# HighwaySchematic.net
KiCad netlist of a schematic drawn in EasyEDA Pro
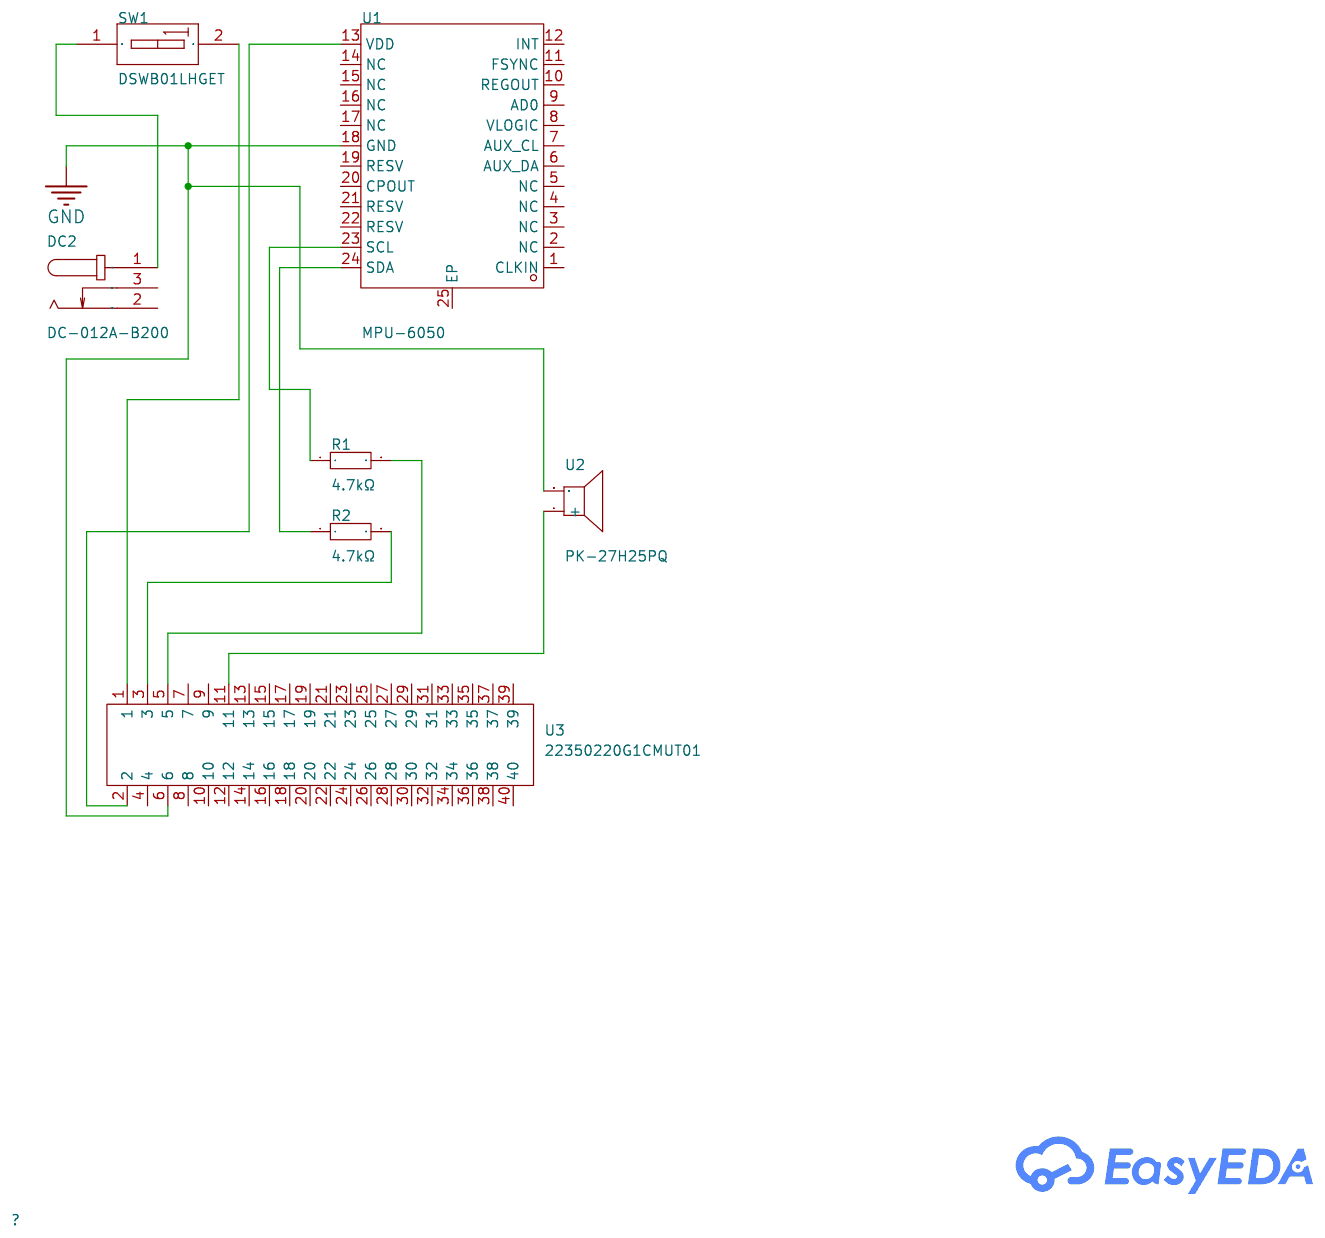
[diagram p0: schematic sheet]

(export (version "E")
  (design (tool "Eeschema 10.0.6"))
  (components
    (comp (ref "DC2")
      (value "DC-012A-B200")
      (footprint "easyedapro:DC-IN-TH_DC-012A-B200")
      (fields (field (name "Manufacturer") "XUNPU(讯普)"))
      (libsource (lib "easyedapro") (part "DC-012A-B200"))
    )
    (comp (ref "R1")
      (value "4.7kΩ")
      (footprint "easyedapro:R0603")
      (fields (field (name "Manufacturer Part") "RC0603FR-074K7L") (field (name "Manufacturer") "YAGEO(国巨)"))
      (libsource (lib "easyedapro") (part "RC0603FR-074K7L"))
    )
    (comp (ref "R2")
      (value "4.7kΩ")
      (footprint "easyedapro:R0603")
      (fields (field (name "Manufacturer Part") "RC0603FR-074K7L") (field (name "Manufacturer") "YAGEO(国巨)"))
      (libsource (lib "easyedapro") (part "RC0603FR-074K7L"))
    )
    (comp (ref "SW1")
      (value "DSWB01LHGET")
      (footprint "easyedapro:SW-TH_DSWB01LHGET")
      (description "Type:平拨,凸起式 Circuit:SPST Number of Positions:1Bit Lead Pitch:- Operating Life:- Color:Red")
      (fields (field (name "Manufacturer") "YE"))
      (libsource (lib "easyedapro") (part "DSWB01LHGET"))
    )
    (comp (ref "U1")
      (value "MPU-6050")
      (footprint "easyedapro:QFN-24_L4.0-W4.0-P0.50-BL-EP2.7")
      (description "Sensor Type:加速度计陀螺仪 Operating Temperature:-40°C~+85°C Operating Temperature:-40°C~+85°C")
      (fields (field (name "Manufacturer") "TDK InvenSense(应美盛)"))
      (libsource (lib "easyedapro") (part "MPU-6050_C24112"))
    )
    (comp (ref "U2")
      (value "PK-27H25PQ")
      (footprint "easyedapro:BUZ-TH_BD30.0-P15.00-D0.8")
      (fields (field (name "Manufacturer") "Mallory Sonalert Products Inc"))
      (libsource (lib "easyedapro") (part "PK-27H25PQ"))
    )
    (comp (ref "U3")
      (value "22350220G1CMUT01")
      (footprint "easyedapro:HDR-SMD_40P-P2.54-V-F-R2-C20-S6.6-EH")
      (libsource (lib "easyedapro") (part "22350220G1CMUT01"))
    )
  )
  (nets
    (net (code "1") (name "GND") (class "Default")
      (node (ref "U1") (pin "18") (pinfunction "GND_18") (pintype "unspecified"))
      (node (ref "U2") (pin "2") (pinfunction "2_2") (pintype "unspecified"))
      (node (ref "U3") (pin "6") (pinfunction "6_6") (pintype "unspecified"))
    )
    (net (code "2") (name "Net-(R1-Pad2)") (class "Default")
      (node (ref "R1") (pin "2") (pinfunction "2_2") (pintype "input"))
      (node (ref "U3") (pin "5") (pinfunction "5_5") (pintype "unspecified"))
    )
    (net (code "3") (name "Net-(R2-Pad2)") (class "Default")
      (node (ref "R2") (pin "2") (pinfunction "2_2") (pintype "input"))
      (node (ref "U3") (pin "3") (pinfunction "3_3") (pintype "unspecified"))
    )
    (net (code "4") (name "Net-(SW1-A1)") (class "Default")
      (node (ref "DC2") (pin "1") (pinfunction "1_1") (pintype "unspecified"))
      (node (ref "SW1") (pin "1") (pinfunction "A1_1") (pintype "input"))
    )
    (net (code "5") (name "Net-(SW1-Pad2)") (class "Default")
      (node (ref "SW1") (pin "2") (pinfunction "2_2") (pintype "input"))
      (node (ref "U3") (pin "1") (pinfunction "1_1") (pintype "unspecified"))
    )
    (net (code "6") (name "Net-(U1-SCL)") (class "Default")
      (node (ref "R1") (pin "1") (pinfunction "1_1") (pintype "input"))
      (node (ref "U1") (pin "23") (pinfunction "SCL_23") (pintype "unspecified"))
    )
    (net (code "7") (name "Net-(U1-SDA)") (class "Default")
      (node (ref "R2") (pin "1") (pinfunction "1_1") (pintype "input"))
      (node (ref "U1") (pin "24") (pinfunction "SDA_24") (pintype "unspecified"))
    )
    (net (code "8") (name "Net-(U1-VDD)") (class "Default")
      (node (ref "U1") (pin "13") (pinfunction "VDD_13") (pintype "unspecified"))
      (node (ref "U3") (pin "2") (pinfunction "2_2") (pintype "unspecified"))
    )
    (net (code "9") (name "Net-(U2-+)") (class "Default")
      (node (ref "U2") (pin "1") (pinfunction "+_1") (pintype "unspecified"))
      (node (ref "U3") (pin "11") (pinfunction "11_11") (pintype "unspecified"))
    )
    (net (code "10") (name "unconnected-(DC2-Pad2)") (class "Default")
      (node (ref "DC2") (pin "2") (pinfunction "2_2") (pintype "unspecified"))
    )
    (net (code "11") (name "unconnected-(DC2-Pad3)") (class "Default")
      (node (ref "DC2") (pin "3") (pinfunction "3_3") (pintype "unspecified"))
    )
    (net (code "12") (name "unconnected-(U1-AD0-Pad9)") (class "Default")
      (node (ref "U1") (pin "9") (pinfunction "AD0_9") (pintype "unspecified"))
    )
    (net (code "13") (name "unconnected-(U1-AUX_CL-Pad7)") (class "Default")
      (node (ref "U1") (pin "7") (pinfunction "AUX_CL_7") (pintype "unspecified"))
    )
    (net (code "14") (name "unconnected-(U1-AUX_DA-Pad6)") (class "Default")
      (node (ref "U1") (pin "6") (pinfunction "AUX_DA_6") (pintype "unspecified"))
    )
    (net (code "15") (name "unconnected-(U1-CLKIN-Pad1)") (class "Default")
      (node (ref "U1") (pin "1") (pinfunction "CLKIN_1") (pintype "unspecified"))
    )
    (net (code "16") (name "unconnected-(U1-CPOUT-Pad20)") (class "Default")
      (node (ref "U1") (pin "20") (pinfunction "CPOUT_20") (pintype "unspecified"))
    )
    (net (code "17") (name "unconnected-(U1-EP-Pad25)") (class "Default")
      (node (ref "U1") (pin "25") (pinfunction "EP_25") (pintype "unspecified"))
    )
    (net (code "18") (name "unconnected-(U1-FSYNC-Pad11)") (class "Default")
      (node (ref "U1") (pin "11") (pinfunction "FSYNC_11") (pintype "unspecified"))
    )
    (net (code "19") (name "unconnected-(U1-INT-Pad12)") (class "Default")
      (node (ref "U1") (pin "12") (pinfunction "INT_12") (pintype "unspecified"))
    )
    (net (code "20") (name "unconnected-(U1-NC-Pad2)") (class "Default")
      (node (ref "U1") (pin "2") (pinfunction "NC_2") (pintype "unspecified"))
    )
    (net (code "21") (name "unconnected-(U1-NC-Pad3)") (class "Default")
      (node (ref "U1") (pin "3") (pinfunction "NC_3") (pintype "unspecified"))
    )
    (net (code "22") (name "unconnected-(U1-NC-Pad4)") (class "Default")
      (node (ref "U1") (pin "4") (pinfunction "NC_4") (pintype "unspecified"))
    )
    (net (code "23") (name "unconnected-(U1-NC-Pad5)") (class "Default")
      (node (ref "U1") (pin "5") (pinfunction "NC_5") (pintype "unspecified"))
    )
    (net (code "24") (name "unconnected-(U1-NC-Pad14)") (class "Default")
      (node (ref "U1") (pin "14") (pinfunction "NC_14") (pintype "unspecified"))
    )
    (net (code "25") (name "unconnected-(U1-NC-Pad15)") (class "Default")
      (node (ref "U1") (pin "15") (pinfunction "NC_15") (pintype "unspecified"))
    )
    (net (code "26") (name "unconnected-(U1-NC-Pad16)") (class "Default")
      (node (ref "U1") (pin "16") (pinfunction "NC_16") (pintype "unspecified"))
    )
    (net (code "27") (name "unconnected-(U1-NC-Pad17)") (class "Default")
      (node (ref "U1") (pin "17") (pinfunction "NC_17") (pintype "unspecified"))
    )
    (net (code "28") (name "unconnected-(U1-REGOUT-Pad10)") (class "Default")
      (node (ref "U1") (pin "10") (pinfunction "REGOUT_10") (pintype "unspecified"))
    )
    (net (code "29") (name "unconnected-(U1-RESV-Pad19)") (class "Default")
      (node (ref "U1") (pin "19") (pinfunction "RESV_19") (pintype "unspecified"))
    )
    (net (code "30") (name "unconnected-(U1-RESV-Pad21)") (class "Default")
      (node (ref "U1") (pin "21") (pinfunction "RESV_21") (pintype "unspecified"))
    )
    (net (code "31") (name "unconnected-(U1-RESV-Pad22)") (class "Default")
      (node (ref "U1") (pin "22") (pinfunction "RESV_22") (pintype "unspecified"))
    )
    (net (code "32") (name "unconnected-(U1-VLOGIC-Pad8)") (class "Default")
      (node (ref "U1") (pin "8") (pinfunction "VLOGIC_8") (pintype "unspecified"))
    )
    (net (code "33") (name "unconnected-(U3-Pad4)") (class "Default")
      (node (ref "U3") (pin "4") (pinfunction "4_4") (pintype "unspecified"))
    )
    (net (code "34") (name "unconnected-(U3-Pad7)") (class "Default")
      (node (ref "U3") (pin "7") (pinfunction "7_7") (pintype "unspecified"))
    )
    (net (code "35") (name "unconnected-(U3-Pad8)") (class "Default")
      (node (ref "U3") (pin "8") (pinfunction "8_8") (pintype "unspecified"))
    )
    (net (code "36") (name "unconnected-(U3-Pad9)") (class "Default")
      (node (ref "U3") (pin "9") (pinfunction "9_9") (pintype "unspecified"))
    )
    (net (code "37") (name "unconnected-(U3-Pad10)") (class "Default")
      (node (ref "U3") (pin "10") (pinfunction "10_10") (pintype "unspecified"))
    )
    (net (code "38") (name "unconnected-(U3-Pad12)") (class "Default")
      (node (ref "U3") (pin "12") (pinfunction "12_12") (pintype "unspecified"))
    )
    (net (code "39") (name "unconnected-(U3-Pad13)") (class "Default")
      (node (ref "U3") (pin "13") (pinfunction "13_13") (pintype "unspecified"))
    )
    (net (code "40") (name "unconnected-(U3-Pad14)") (class "Default")
      (node (ref "U3") (pin "14") (pinfunction "14_14") (pintype "unspecified"))
    )
    (net (code "41") (name "unconnected-(U3-Pad15)") (class "Default")
      (node (ref "U3") (pin "15") (pinfunction "15_15") (pintype "unspecified"))
    )
    (net (code "42") (name "unconnected-(U3-Pad16)") (class "Default")
      (node (ref "U3") (pin "16") (pinfunction "16_16") (pintype "unspecified"))
    )
    (net (code "43") (name "unconnected-(U3-Pad17)") (class "Default")
      (node (ref "U3") (pin "17") (pinfunction "17_17") (pintype "unspecified"))
    )
    (net (code "44") (name "unconnected-(U3-Pad18)") (class "Default")
      (node (ref "U3") (pin "18") (pinfunction "18_18") (pintype "unspecified"))
    )
    (net (code "45") (name "unconnected-(U3-Pad19)") (class "Default")
      (node (ref "U3") (pin "19") (pinfunction "19_19") (pintype "unspecified"))
    )
    (net (code "46") (name "unconnected-(U3-Pad20)") (class "Default")
      (node (ref "U3") (pin "20") (pinfunction "20_20") (pintype "unspecified"))
    )
    (net (code "47") (name "unconnected-(U3-Pad21)") (class "Default")
      (node (ref "U3") (pin "21") (pinfunction "21_21") (pintype "unspecified"))
    )
    (net (code "48") (name "unconnected-(U3-Pad22)") (class "Default")
      (node (ref "U3") (pin "22") (pinfunction "22_22") (pintype "unspecified"))
    )
    (net (code "49") (name "unconnected-(U3-Pad23)") (class "Default")
      (node (ref "U3") (pin "23") (pinfunction "23_23") (pintype "unspecified"))
    )
    (net (code "50") (name "unconnected-(U3-Pad24)") (class "Default")
      (node (ref "U3") (pin "24") (pinfunction "24_24") (pintype "unspecified"))
    )
    (net (code "51") (name "unconnected-(U3-Pad25)") (class "Default")
      (node (ref "U3") (pin "25") (pinfunction "25_25") (pintype "unspecified"))
    )
    (net (code "52") (name "unconnected-(U3-Pad26)") (class "Default")
      (node (ref "U3") (pin "26") (pinfunction "26_26") (pintype "unspecified"))
    )
    (net (code "53") (name "unconnected-(U3-Pad27)") (class "Default")
      (node (ref "U3") (pin "27") (pinfunction "27_27") (pintype "unspecified"))
    )
    (net (code "54") (name "unconnected-(U3-Pad28)") (class "Default")
      (node (ref "U3") (pin "28") (pinfunction "28_28") (pintype "unspecified"))
    )
    (net (code "55") (name "unconnected-(U3-Pad29)") (class "Default")
      (node (ref "U3") (pin "29") (pinfunction "29_29") (pintype "unspecified"))
    )
    (net (code "56") (name "unconnected-(U3-Pad30)") (class "Default")
      (node (ref "U3") (pin "30") (pinfunction "30_30") (pintype "unspecified"))
    )
    (net (code "57") (name "unconnected-(U3-Pad31)") (class "Default")
      (node (ref "U3") (pin "31") (pinfunction "31_31") (pintype "unspecified"))
    )
    (net (code "58") (name "unconnected-(U3-Pad32)") (class "Default")
      (node (ref "U3") (pin "32") (pinfunction "32_32") (pintype "unspecified"))
    )
    (net (code "59") (name "unconnected-(U3-Pad33)") (class "Default")
      (node (ref "U3") (pin "33") (pinfunction "33_33") (pintype "unspecified"))
    )
    (net (code "60") (name "unconnected-(U3-Pad34)") (class "Default")
      (node (ref "U3") (pin "34") (pinfunction "34_34") (pintype "unspecified"))
    )
    (net (code "61") (name "unconnected-(U3-Pad35)") (class "Default")
      (node (ref "U3") (pin "35") (pinfunction "35_35") (pintype "unspecified"))
    )
    (net (code "62") (name "unconnected-(U3-Pad36)") (class "Default")
      (node (ref "U3") (pin "36") (pinfunction "36_36") (pintype "unspecified"))
    )
    (net (code "63") (name "unconnected-(U3-Pad37)") (class "Default")
      (node (ref "U3") (pin "37") (pinfunction "37_37") (pintype "unspecified"))
    )
    (net (code "64") (name "unconnected-(U3-Pad38)") (class "Default")
      (node (ref "U3") (pin "38") (pinfunction "38_38") (pintype "unspecified"))
    )
    (net (code "65") (name "unconnected-(U3-Pad39)") (class "Default")
      (node (ref "U3") (pin "39") (pinfunction "39_39") (pintype "unspecified"))
    )
    (net (code "66") (name "unconnected-(U3-Pad40)") (class "Default")
      (node (ref "U3") (pin "40") (pinfunction "40_40") (pintype "unspecified"))
    )
  )
)
